# USBIF_v1.net
KiCad netlist of a schematic drawn in EAGLE
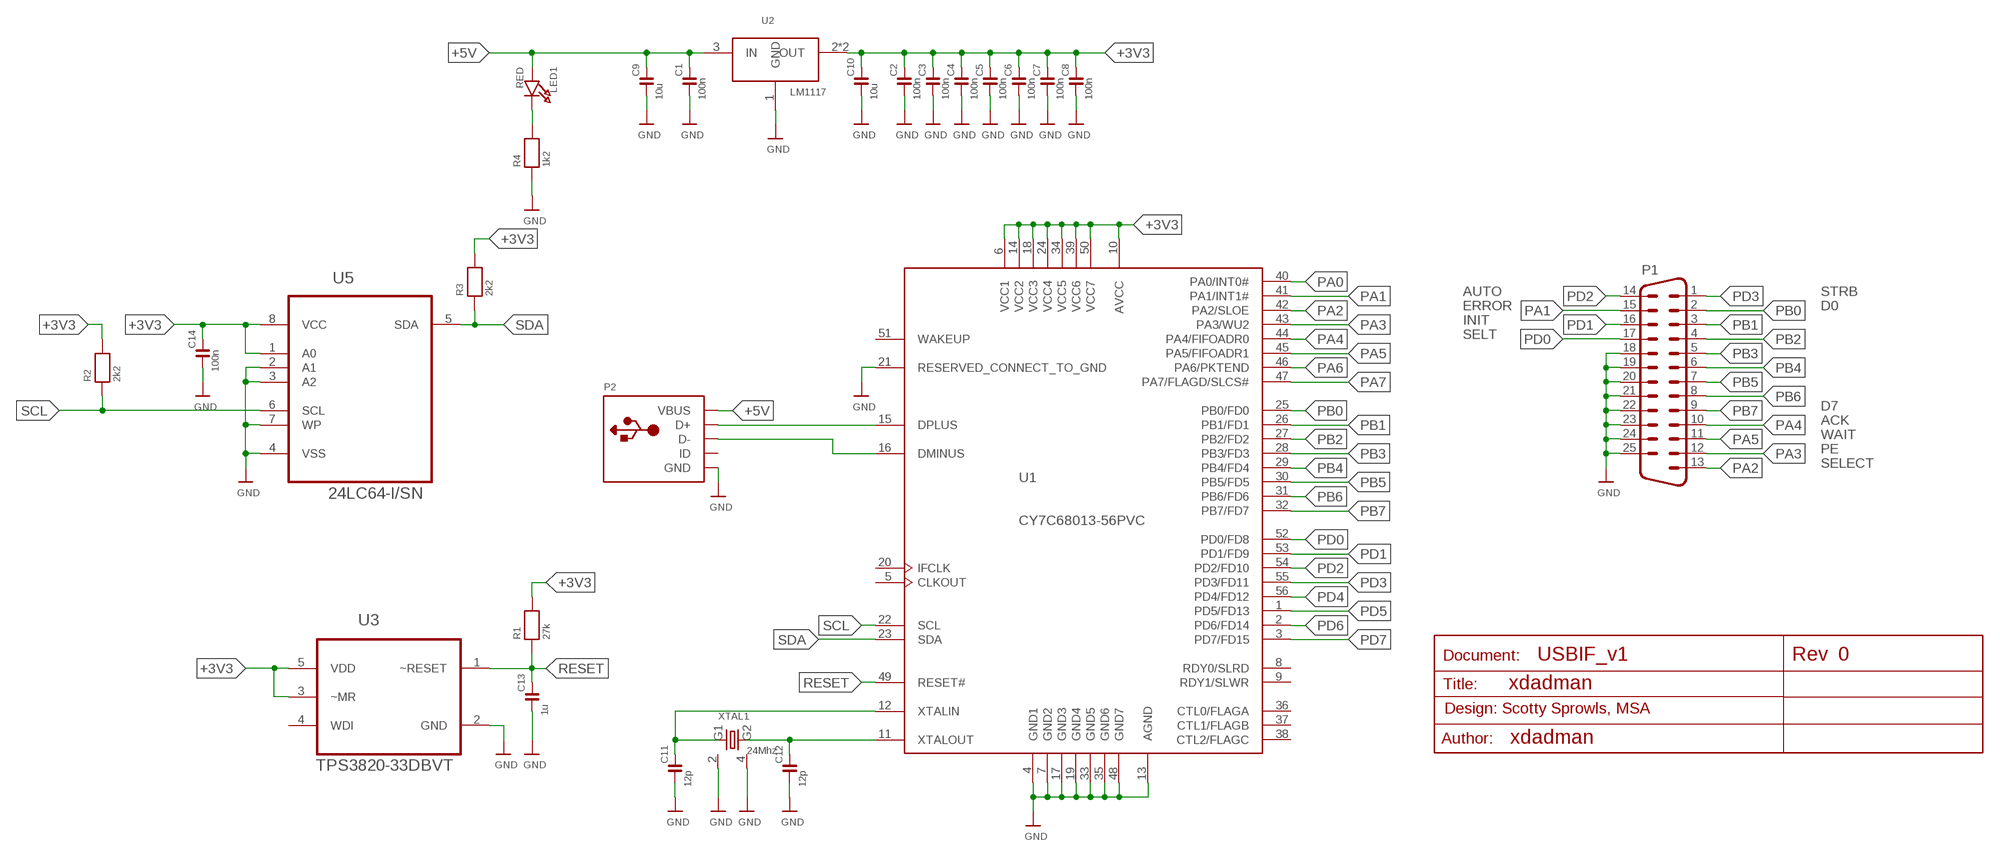
[diagram p0: schematic, sheet 1]

(export (version "E")
  (design (tool "Eeschema 10.0.6"))
  (components
    (comp (ref "C1")
      (value "100n")
      (footprint "eagle-import:C0805")
      (libsource (lib "eagle-import") (part "C0805100N"))
    )
    (comp (ref "C2")
      (value "100n")
      (footprint "eagle-import:C0603")
      (libsource (lib "eagle-import") (part "CC0603100NF"))
    )
    (comp (ref "C3")
      (value "100n")
      (footprint "eagle-import:C0603")
      (libsource (lib "eagle-import") (part "CC0603100NF"))
    )
    (comp (ref "C4")
      (value "100n")
      (footprint "eagle-import:C0603")
      (libsource (lib "eagle-import") (part "CC0603100NF"))
    )
    (comp (ref "C5")
      (value "100n")
      (footprint "eagle-import:C0603")
      (libsource (lib "eagle-import") (part "CC0603100NF"))
    )
    (comp (ref "C6")
      (value "100n")
      (footprint "eagle-import:C0603")
      (libsource (lib "eagle-import") (part "CC0603100NF"))
    )
    (comp (ref "C7")
      (value "100n")
      (footprint "eagle-import:C0603")
      (libsource (lib "eagle-import") (part "CC0603100NF"))
    )
    (comp (ref "C8")
      (value "100n")
      (footprint "eagle-import:C0603")
      (libsource (lib "eagle-import") (part "CC0603100NF"))
    )
    (comp (ref "C9")
      (value "10u")
      (footprint "eagle-import:C1206")
      (libsource (lib "eagle-import") (part "CC120610U"))
    )
    (comp (ref "C10")
      (value "10u")
      (footprint "eagle-import:C1206")
      (libsource (lib "eagle-import") (part "CC120610U"))
    )
    (comp (ref "C11")
      (value "12p")
      (footprint "eagle-import:C0603")
      (libsource (lib "eagle-import") (part "CC060312P"))
    )
    (comp (ref "C12")
      (value "12p")
      (footprint "eagle-import:C0603")
      (libsource (lib "eagle-import") (part "CC060312P"))
    )
    (comp (ref "C13")
      (value "1u")
      (footprint "eagle-import:C0805")
      (libsource (lib "eagle-import") (part "C08051UF"))
    )
    (comp (ref "C14")
      (value "100n")
      (footprint "eagle-import:C0603")
      (libsource (lib "eagle-import") (part "CC0603100NF"))
    )
    (comp (ref "LED1")
      (value "RED")
      (footprint "eagle-import:CHIPLED_0603")
      (libsource (lib "eagle-import") (part "LED_0603_RED0603"))
    )
    (comp (ref "P1")
      (value "M25D")
      (footprint "eagle-import:M25D")
      (libsource (lib "eagle-import") (part "M25D"))
    )
    (comp (ref "P2")
      (value "USBMINIBLARGE")
      (footprint "eagle-import:USB-MINIB_LARGER")
      (libsource (lib "eagle-import") (part "USBMINIBLARGE"))
    )
    (comp (ref "R1")
      (value "27k")
      (footprint "eagle-import:R0805")
      (libsource (lib "eagle-import") (part "R080527K"))
    )
    (comp (ref "R2")
      (value "2k2")
      (footprint "eagle-import:R0805")
      (libsource (lib "eagle-import") (part "R08052K2"))
    )
    (comp (ref "R3")
      (value "2k2")
      (footprint "eagle-import:R0805")
      (libsource (lib "eagle-import") (part "R08052K2"))
    )
    (comp (ref "R4")
      (value "1k2")
      (footprint "eagle-import:R0805")
      (libsource (lib "eagle-import") (part "R08051K2"))
    )
    (comp (ref "U1")
      (value "CY7C68013-56PVC")
      (footprint "eagle-import:SSOP-56")
      (libsource (lib "eagle-import") (part "CY7C68013-56PVC"))
    )
    (comp (ref "U2")
      (value "LM1117")
      (footprint "eagle-import:SOT223")
      (libsource (lib "eagle-import") (part "LM1117"))
    )
    (comp (ref "U3")
      (value "TPS3820-33DBVT")
      (footprint "eagle-import:SOT95P280X145-5N")
      (libsource (lib "eagle-import") (part "TPS3820-33DBVT"))
    )
    (comp (ref "U5")
      (value "24LC64-I/SN")
      (footprint "eagle-import:SOIC127P600X175-8N_JDA2")
      (libsource (lib "eagle-import") (part "24LC64-I/SN"))
    )
    (comp (ref "XTAL1")
      (value "24Mhz")
      (footprint "eagle-import:AKER_7X5")
      (libsource (lib "eagle-import") (part "AKER_C7S-24.000-12-3030-X"))
    )
  )
  (nets
    (net (code "1") (name "+3V3") (class "Default")
      (node (ref "C10") (pin "2") (pinfunction "2_2") (pintype "passive"))
      (node (ref "C14") (pin "2") (pinfunction "2_2") (pintype "passive"))
      (node (ref "C2") (pin "2") (pinfunction "2_2") (pintype "passive"))
      (node (ref "C3") (pin "2") (pinfunction "2_2") (pintype "passive"))
      (node (ref "C4") (pin "2") (pinfunction "2_2") (pintype "passive"))
      (node (ref "C5") (pin "2") (pinfunction "2_2") (pintype "passive"))
      (node (ref "C6") (pin "2") (pinfunction "2_2") (pintype "passive"))
      (node (ref "C7") (pin "2") (pinfunction "2_2") (pintype "passive"))
      (node (ref "C8") (pin "2") (pinfunction "2_2") (pintype "passive"))
      (node (ref "R1") (pin "2") (pinfunction "2_2") (pintype "passive"))
      (node (ref "R2") (pin "2") (pinfunction "2_2") (pintype "passive"))
      (node (ref "R3") (pin "2") (pinfunction "2_2") (pintype "passive"))
      (node (ref "U1") (pin "10") (pinfunction "AVCC_10") (pintype "bidirectional"))
      (node (ref "U1") (pin "14") (pinfunction "VCC2_14") (pintype "bidirectional"))
      (node (ref "U1") (pin "18") (pinfunction "VCC3_18") (pintype "bidirectional"))
      (node (ref "U1") (pin "24") (pinfunction "VCC4_24") (pintype "bidirectional"))
      (node (ref "U1") (pin "34") (pinfunction "VCC5_34") (pintype "bidirectional"))
      (node (ref "U1") (pin "39") (pinfunction "VCC6_39") (pintype "bidirectional"))
      (node (ref "U1") (pin "50") (pinfunction "VCC7_50") (pintype "bidirectional"))
      (node (ref "U1") (pin "6") (pinfunction "VCC1_6") (pintype "bidirectional"))
      (node (ref "U2") (pin "2") (pinfunction "OUT_2") (pintype "bidirectional"))
      (node (ref "U2") (pin "4") (pinfunction "OUT_4") (pintype "bidirectional"))
      (node (ref "U3") (pin "3") (pinfunction "~{MR}_3") (pintype "input"))
      (node (ref "U3") (pin "5") (pinfunction "VDD_5") (pintype "power_in"))
      (node (ref "U5") (pin "1") (pinfunction "A0_1") (pintype "input"))
      (node (ref "U5") (pin "8") (pinfunction "VCC_8") (pintype "power_in"))
    )
    (net (code "2") (name "+5V") (class "Default")
      (node (ref "C1") (pin "2") (pinfunction "2_2") (pintype "passive"))
      (node (ref "C9") (pin "2") (pinfunction "2_2") (pintype "passive"))
      (node (ref "LED1") (pin "A") (pinfunction "A_A") (pintype "passive"))
      (node (ref "P2") (pin "VBUS") (pinfunction "VBUS_VBUS") (pintype "power_in"))
      (node (ref "U2") (pin "3") (pinfunction "IN_3") (pintype "bidirectional"))
    )
    (net (code "3") (name "GND") (class "Default")
      (node (ref "C1") (pin "1") (pinfunction "1_1") (pintype "passive"))
      (node (ref "C10") (pin "1") (pinfunction "1_1") (pintype "passive"))
      (node (ref "C11") (pin "1") (pinfunction "1_1") (pintype "passive"))
      (node (ref "C12") (pin "1") (pinfunction "1_1") (pintype "passive"))
      (node (ref "C13") (pin "1") (pinfunction "1_1") (pintype "passive"))
      (node (ref "C14") (pin "1") (pinfunction "1_1") (pintype "passive"))
      (node (ref "C2") (pin "1") (pinfunction "1_1") (pintype "passive"))
      (node (ref "C3") (pin "1") (pinfunction "1_1") (pintype "passive"))
      (node (ref "C4") (pin "1") (pinfunction "1_1") (pintype "passive"))
      (node (ref "C5") (pin "1") (pinfunction "1_1") (pintype "passive"))
      (node (ref "C6") (pin "1") (pinfunction "1_1") (pintype "passive"))
      (node (ref "C7") (pin "1") (pinfunction "1_1") (pintype "passive"))
      (node (ref "C8") (pin "1") (pinfunction "1_1") (pintype "passive"))
      (node (ref "C9") (pin "1") (pinfunction "1_1") (pintype "passive"))
      (node (ref "P1") (pin "18") (pinfunction "18_18") (pintype "passive"))
      (node (ref "P1") (pin "19") (pinfunction "19_19") (pintype "passive"))
      (node (ref "P1") (pin "20") (pinfunction "20_20") (pintype "passive"))
      (node (ref "P1") (pin "21") (pinfunction "21_21") (pintype "passive"))
      (node (ref "P1") (pin "22") (pinfunction "22_22") (pintype "passive"))
      (node (ref "P1") (pin "23") (pinfunction "23_23") (pintype "passive"))
      (node (ref "P1") (pin "24") (pinfunction "24_24") (pintype "passive"))
      (node (ref "P1") (pin "25") (pinfunction "25_25") (pintype "passive"))
      (node (ref "P2") (pin "GND") (pinfunction "GND_GND") (pintype "power_in"))
      (node (ref "R4") (pin "1") (pinfunction "1_1") (pintype "passive"))
      (node (ref "U1") (pin "13") (pinfunction "AGND_13") (pintype "bidirectional"))
      (node (ref "U1") (pin "17") (pinfunction "GND3_17") (pintype "bidirectional"))
      (node (ref "U1") (pin "19") (pinfunction "GND4_19") (pintype "bidirectional"))
      (node (ref "U1") (pin "21") (pinfunction "RESERVED_CONNECT_TO_GND_21") (pintype "input"))
      (node (ref "U1") (pin "33") (pinfunction "GND5_33") (pintype "bidirectional"))
      (node (ref "U1") (pin "35") (pinfunction "GND6_35") (pintype "bidirectional"))
      (node (ref "U1") (pin "4") (pinfunction "GND1_4") (pintype "bidirectional"))
      (node (ref "U1") (pin "48") (pinfunction "GND7_48") (pintype "bidirectional"))
      (node (ref "U1") (pin "7") (pinfunction "GND2_7") (pintype "bidirectional"))
      (node (ref "U2") (pin "1") (pinfunction "GND_1") (pintype "bidirectional"))
      (node (ref "U3") (pin "2") (pinfunction "GND_2") (pintype "passive"))
      (node (ref "U5") (pin "2") (pinfunction "A1_2") (pintype "input"))
      (node (ref "U5") (pin "3") (pinfunction "A2_3") (pintype "input"))
      (node (ref "U5") (pin "4") (pinfunction "VSS_4") (pintype "passive"))
      (node (ref "U5") (pin "7") (pinfunction "WP_7") (pintype "input"))
      (node (ref "XTAL1") (pin "2") (pinfunction "G1_2") (pintype "passive"))
      (node (ref "XTAL1") (pin "4") (pinfunction "G2_4") (pintype "passive"))
    )
    (net (code "4") (name "Net-(LED1-PadC)") (class "Default")
      (node (ref "LED1") (pin "C") (pinfunction "C_C") (pintype "passive"))
      (node (ref "R4") (pin "2") (pinfunction "2_2") (pintype "passive"))
    )
    (net (code "5") (name "Net-(U1-DMINUS)") (class "Default")
      (node (ref "P2") (pin "D-") (pinfunction "D-_D-") (pintype "bidirectional"))
      (node (ref "U1") (pin "16") (pinfunction "DMINUS_16") (pintype "bidirectional"))
    )
    (net (code "6") (name "Net-(U1-DPLUS)") (class "Default")
      (node (ref "P2") (pin "D+") (pinfunction "D+_D+") (pintype "bidirectional"))
      (node (ref "U1") (pin "15") (pinfunction "DPLUS_15") (pintype "bidirectional"))
    )
    (net (code "7") (name "Net-(U1-XTALIN)") (class "Default")
      (node (ref "C11") (pin "2") (pinfunction "2_2") (pintype "passive"))
      (node (ref "U1") (pin "12") (pinfunction "XTALIN_12") (pintype "bidirectional"))
      (node (ref "XTAL1") (pin "1") (pinfunction "S1_1") (pintype "passive"))
    )
    (net (code "8") (name "Net-(U1-XTALOUT)") (class "Default")
      (node (ref "C12") (pin "2") (pinfunction "2_2") (pintype "passive"))
      (node (ref "U1") (pin "11") (pinfunction "XTALOUT_11") (pintype "bidirectional"))
      (node (ref "XTAL1") (pin "3") (pinfunction "S2_3") (pintype "passive"))
    )
    (net (code "9") (name "PA0") (class "Default")
      (node (ref "U1") (pin "40") (pinfunction "PA0/INT0#_40") (pintype "bidirectional"))
    )
    (net (code "10") (name "PA1") (class "Default")
      (node (ref "P1") (pin "15") (pinfunction "15_15") (pintype "passive"))
      (node (ref "U1") (pin "41") (pinfunction "PA1/INT1#_41") (pintype "bidirectional"))
    )
    (net (code "11") (name "PA2") (class "Default")
      (node (ref "P1") (pin "13") (pinfunction "13_13") (pintype "passive"))
      (node (ref "U1") (pin "42") (pinfunction "PA2/SLOE_42") (pintype "bidirectional"))
    )
    (net (code "12") (name "PA3") (class "Default")
      (node (ref "P1") (pin "12") (pinfunction "12_12") (pintype "passive"))
      (node (ref "U1") (pin "43") (pinfunction "PA3/WU2_43") (pintype "bidirectional"))
    )
    (net (code "13") (name "PA4") (class "Default")
      (node (ref "P1") (pin "10") (pinfunction "10_10") (pintype "passive"))
      (node (ref "U1") (pin "44") (pinfunction "PA4/FIFOADR0_44") (pintype "bidirectional"))
    )
    (net (code "14") (name "PA5") (class "Default")
      (node (ref "P1") (pin "11") (pinfunction "11_11") (pintype "passive"))
      (node (ref "U1") (pin "45") (pinfunction "PA5/FIFOADR1_45") (pintype "bidirectional"))
    )
    (net (code "15") (name "PA6") (class "Default")
      (node (ref "U1") (pin "46") (pinfunction "PA6/PKTEND_46") (pintype "bidirectional"))
    )
    (net (code "16") (name "PA7") (class "Default")
      (node (ref "U1") (pin "47") (pinfunction "PA7/FLAGD/SLCS#_47") (pintype "bidirectional"))
    )
    (net (code "17") (name "PB0") (class "Default")
      (node (ref "P1") (pin "2") (pinfunction "2_2") (pintype "passive"))
      (node (ref "U1") (pin "25") (pinfunction "PB0/FD0_25") (pintype "bidirectional"))
    )
    (net (code "18") (name "PB1") (class "Default")
      (node (ref "P1") (pin "3") (pinfunction "3_3") (pintype "passive"))
      (node (ref "U1") (pin "26") (pinfunction "PB1/FD1_26") (pintype "bidirectional"))
    )
    (net (code "19") (name "PB2") (class "Default")
      (node (ref "P1") (pin "4") (pinfunction "4_4") (pintype "passive"))
      (node (ref "U1") (pin "27") (pinfunction "PB2/FD2_27") (pintype "bidirectional"))
    )
    (net (code "20") (name "PB3") (class "Default")
      (node (ref "P1") (pin "5") (pinfunction "5_5") (pintype "passive"))
      (node (ref "U1") (pin "28") (pinfunction "PB3/FD3_28") (pintype "bidirectional"))
    )
    (net (code "21") (name "PB4") (class "Default")
      (node (ref "P1") (pin "6") (pinfunction "6_6") (pintype "passive"))
      (node (ref "U1") (pin "29") (pinfunction "PB4/FD4_29") (pintype "bidirectional"))
    )
    (net (code "22") (name "PB5") (class "Default")
      (node (ref "P1") (pin "7") (pinfunction "7_7") (pintype "passive"))
      (node (ref "U1") (pin "30") (pinfunction "PB5/FD5_30") (pintype "bidirectional"))
    )
    (net (code "23") (name "PB6") (class "Default")
      (node (ref "P1") (pin "8") (pinfunction "8_8") (pintype "passive"))
      (node (ref "U1") (pin "31") (pinfunction "PB6/FD6_31") (pintype "bidirectional"))
    )
    (net (code "24") (name "PB7") (class "Default")
      (node (ref "P1") (pin "9") (pinfunction "9_9") (pintype "passive"))
      (node (ref "U1") (pin "32") (pinfunction "PB7/FD7_32") (pintype "bidirectional"))
    )
    (net (code "25") (name "PD0") (class "Default")
      (node (ref "P1") (pin "17") (pinfunction "17_17") (pintype "passive"))
      (node (ref "U1") (pin "52") (pinfunction "PD0/FD8_52") (pintype "bidirectional"))
    )
    (net (code "26") (name "PD1") (class "Default")
      (node (ref "P1") (pin "16") (pinfunction "16_16") (pintype "passive"))
      (node (ref "U1") (pin "53") (pinfunction "PD1/FD9_53") (pintype "bidirectional"))
    )
    (net (code "27") (name "PD2") (class "Default")
      (node (ref "P1") (pin "14") (pinfunction "14_14") (pintype "passive"))
      (node (ref "U1") (pin "54") (pinfunction "PD2/FD10_54") (pintype "bidirectional"))
    )
    (net (code "28") (name "PD3") (class "Default")
      (node (ref "P1") (pin "1") (pinfunction "1_1") (pintype "passive"))
      (node (ref "U1") (pin "55") (pinfunction "PD3/FD11_55") (pintype "bidirectional"))
    )
    (net (code "29") (name "PD4") (class "Default")
      (node (ref "U1") (pin "56") (pinfunction "PD4/FD12_56") (pintype "bidirectional"))
    )
    (net (code "30") (name "PD5") (class "Default")
      (node (ref "U1") (pin "1") (pinfunction "PD5/FD13_1") (pintype "bidirectional"))
    )
    (net (code "31") (name "PD6") (class "Default")
      (node (ref "U1") (pin "2") (pinfunction "PD6/FD14_2") (pintype "bidirectional"))
    )
    (net (code "32") (name "PD7") (class "Default")
      (node (ref "U1") (pin "3") (pinfunction "PD7/FD15_3") (pintype "bidirectional"))
    )
    (net (code "33") (name "RESET") (class "Default")
      (node (ref "C13") (pin "2") (pinfunction "2_2") (pintype "passive"))
      (node (ref "R1") (pin "1") (pinfunction "1_1") (pintype "passive"))
      (node (ref "U1") (pin "49") (pinfunction "RESET#_49") (pintype "input"))
      (node (ref "U3") (pin "1") (pinfunction "~{RESET}_1") (pintype "output"))
    )
    (net (code "34") (name "SCL") (class "Default")
      (node (ref "R2") (pin "1") (pinfunction "1_1") (pintype "passive"))
      (node (ref "U1") (pin "22") (pinfunction "SCL_22") (pintype "bidirectional"))
      (node (ref "U5") (pin "6") (pinfunction "SCL_6") (pintype "input"))
    )
    (net (code "35") (name "SDA") (class "Default")
      (node (ref "R3") (pin "1") (pinfunction "1_1") (pintype "passive"))
      (node (ref "U1") (pin "23") (pinfunction "SDA_23") (pintype "bidirectional"))
      (node (ref "U5") (pin "5") (pinfunction "SDA_5") (pintype "bidirectional"))
    )
    (net (code "36") (name "unconnected-(P2-PadID)") (class "Default")
      (node (ref "P2") (pin "ID") (pinfunction "ID_ID") (pintype "bidirectional"))
    )
    (net (code "37") (name "unconnected-(U1-CLKOUT-Pad5)") (class "Default")
      (node (ref "U1") (pin "5") (pinfunction "CLKOUT_5") (pintype "output"))
    )
    (net (code "38") (name "unconnected-(U1-CTL0{slash}FLAGA-Pad36)") (class "Default")
      (node (ref "U1") (pin "36") (pinfunction "CTL0/FLAGA_36") (pintype "bidirectional"))
    )
    (net (code "39") (name "unconnected-(U1-CTL1{slash}FLAGB-Pad37)") (class "Default")
      (node (ref "U1") (pin "37") (pinfunction "CTL1/FLAGB_37") (pintype "bidirectional"))
    )
    (net (code "40") (name "unconnected-(U1-CTL2{slash}FLAGC-Pad38)") (class "Default")
      (node (ref "U1") (pin "38") (pinfunction "CTL2/FLAGC_38") (pintype "bidirectional"))
    )
    (net (code "41") (name "unconnected-(U1-IFCLK-Pad20)") (class "Default")
      (node (ref "U1") (pin "20") (pinfunction "IFCLK_20") (pintype "bidirectional"))
    )
    (net (code "42") (name "unconnected-(U1-RDY0{slash}SLRD-Pad8)") (class "Default")
      (node (ref "U1") (pin "8") (pinfunction "RDY0/SLRD_8") (pintype "bidirectional"))
    )
    (net (code "43") (name "unconnected-(U1-RDY1{slash}SLWR-Pad9)") (class "Default")
      (node (ref "U1") (pin "9") (pinfunction "RDY1/SLWR_9") (pintype "bidirectional"))
    )
    (net (code "44") (name "unconnected-(U1-WAKEUP-Pad51)") (class "Default")
      (node (ref "U1") (pin "51") (pinfunction "WAKEUP_51") (pintype "bidirectional"))
    )
    (net (code "45") (name "unconnected-(U3-WDI-Pad4)") (class "Default")
      (node (ref "U3") (pin "4") (pinfunction "WDI_4") (pintype "input"))
    )
  )
)
